# AUDIO_CODEC.net
KiCad netlist of a schematic drawn in Altium Designer
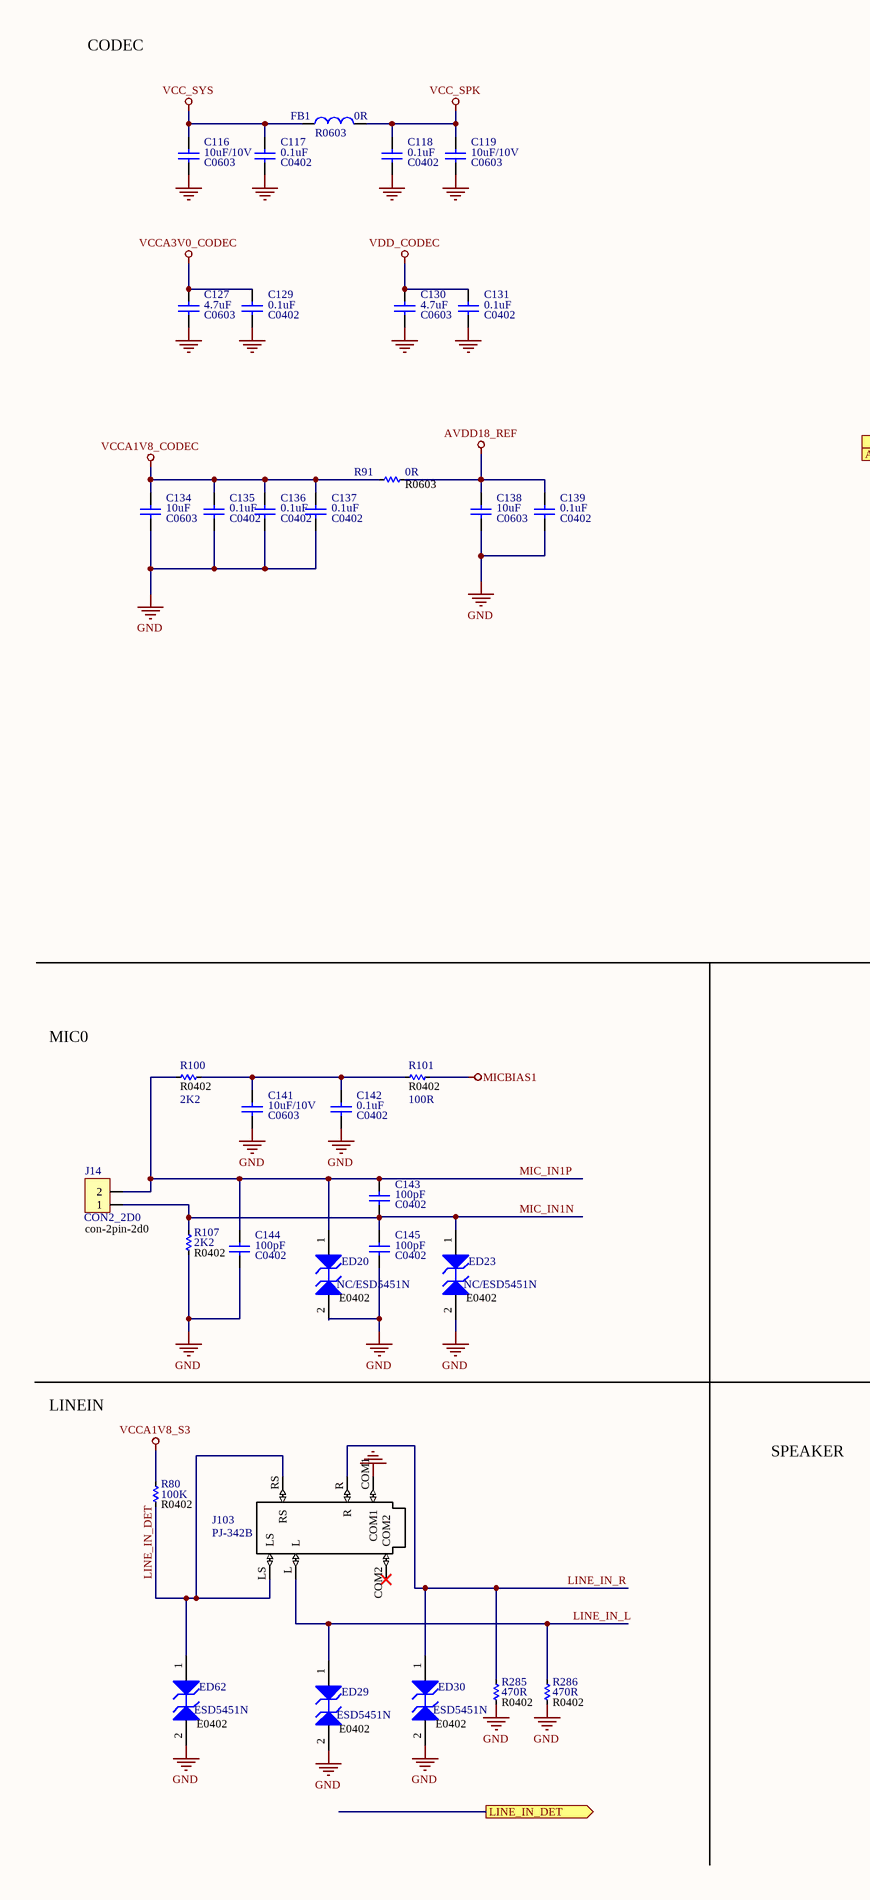
[diagram p0: AUDIO_CODEC.SchDoc, left]
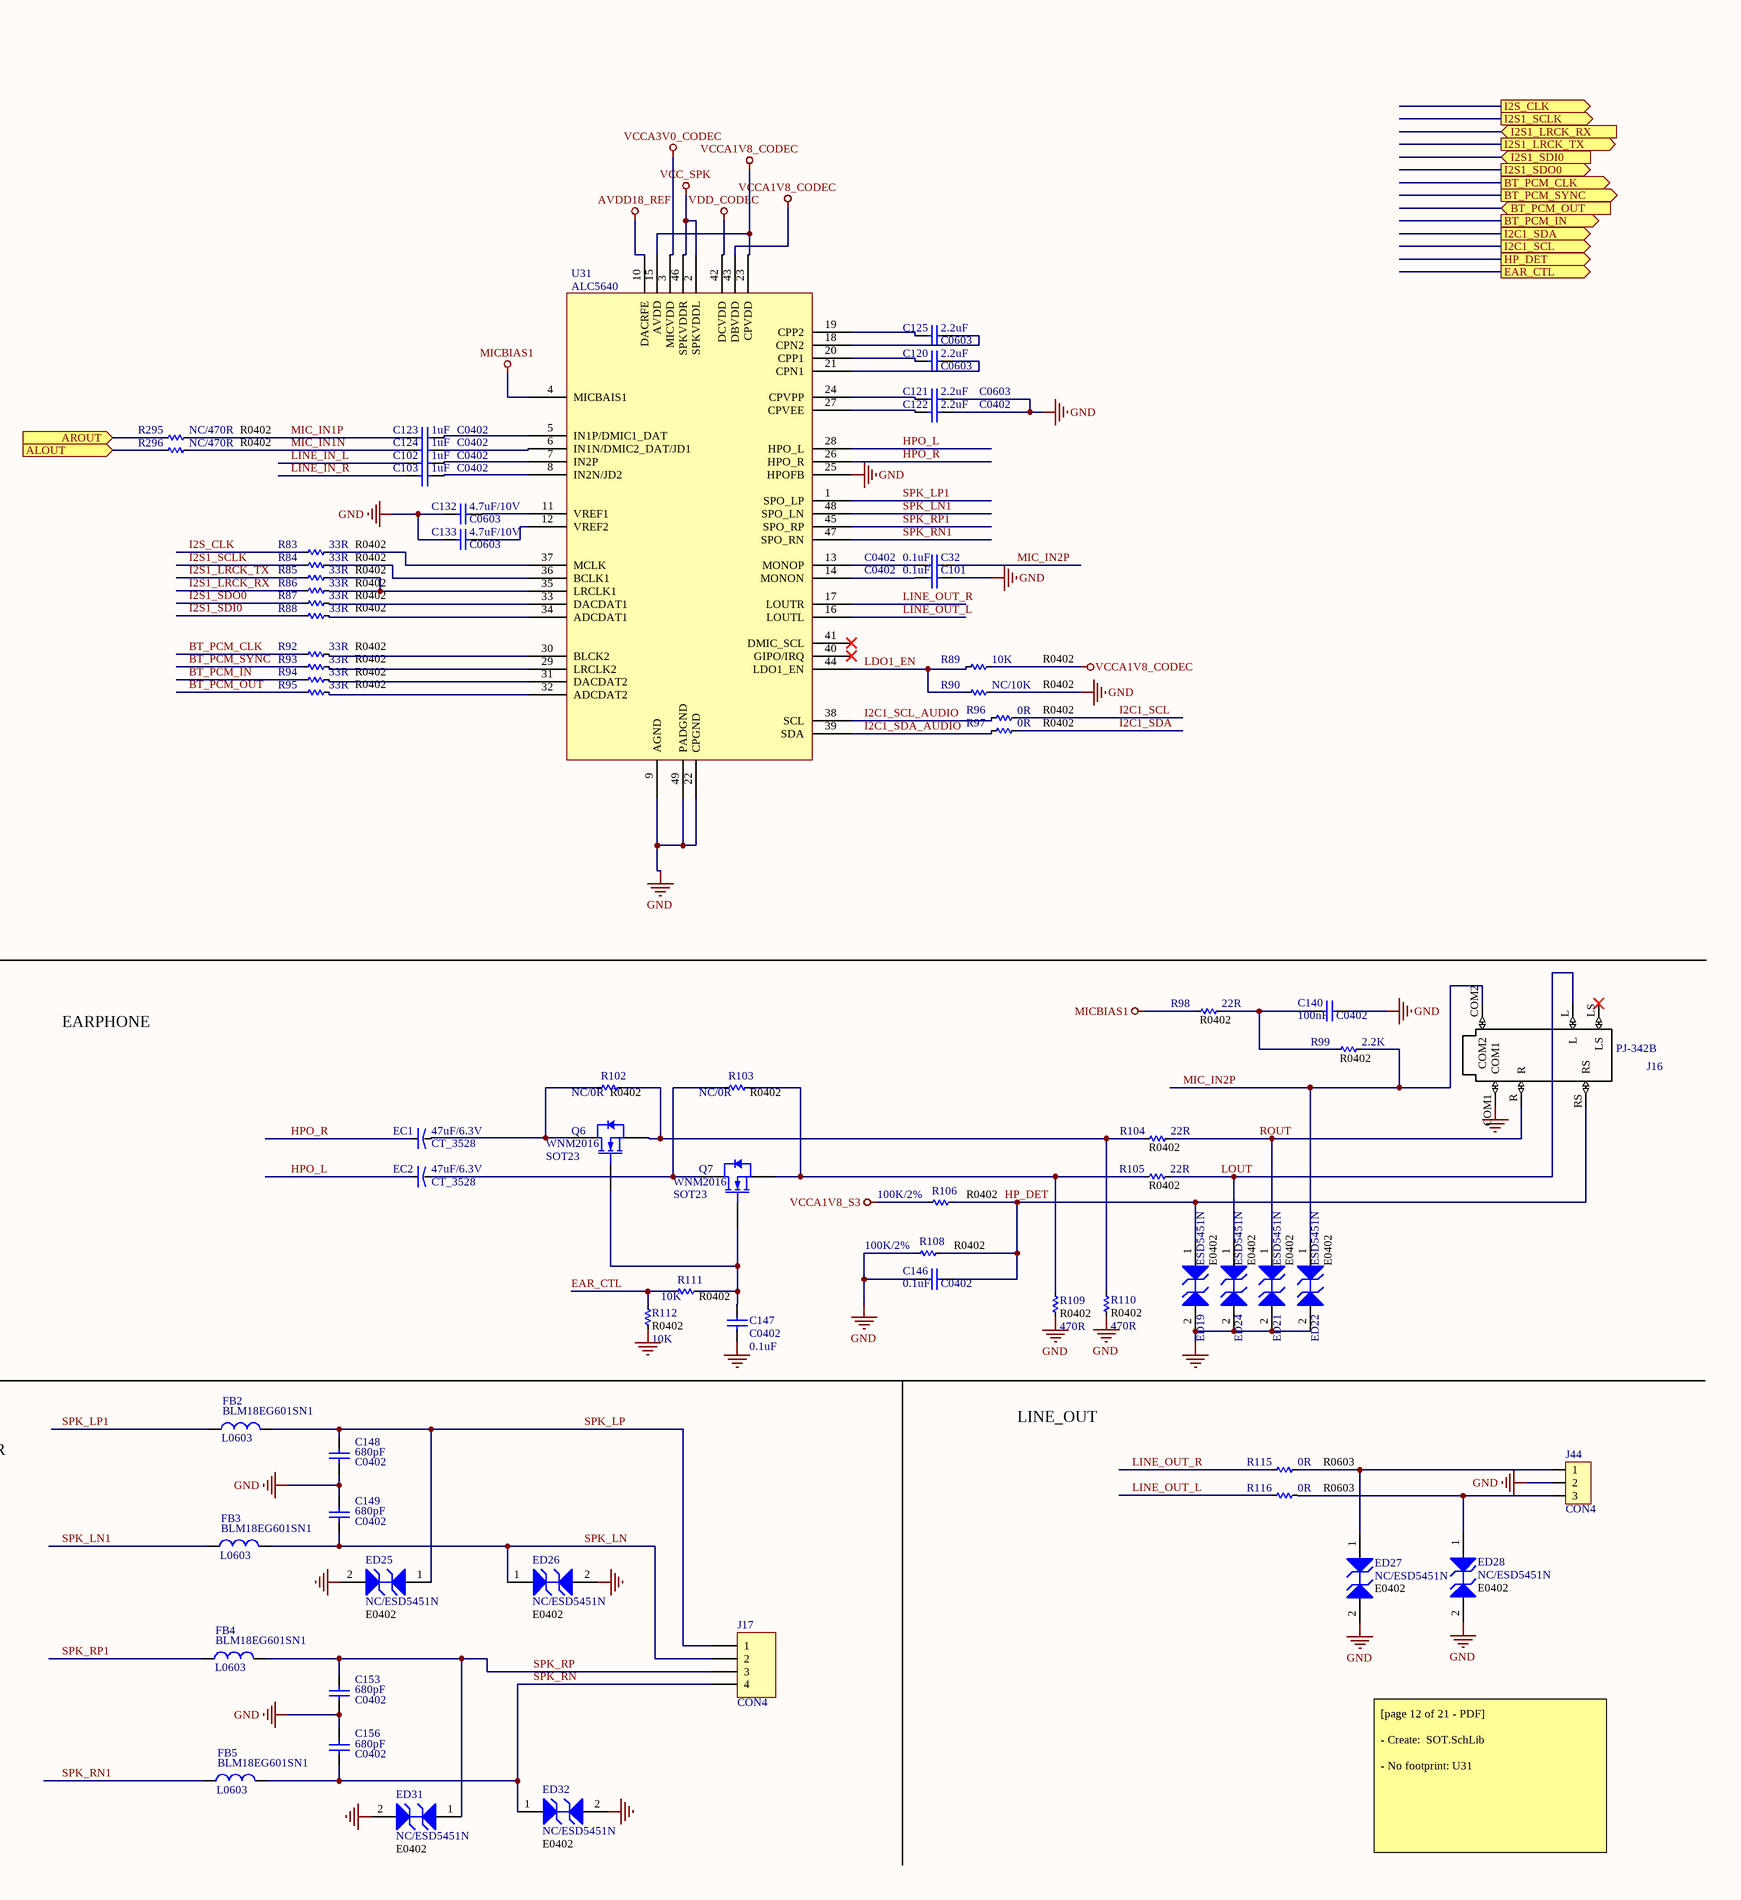
[diagram p1: AUDIO_CODEC.SchDoc, right]

(export (version "E")
  (design (tool "Eeschema 10.0.6"))
  (components
    (comp (ref "C32")
      (value "C0402")
      (footprint "C 0402")
      (description "Capacitor")
      (fields (field (name "ALTIUM_VALUE") "0.1uF") (field (name "PUBLISHER") "Altium Limited"))
      (libsource (lib "Miscellaneous Devices") (part "Cap"))
    )
    (comp (ref "C101")
      (value "C0402")
      (footprint "C 0402")
      (description "Capacitor")
      (fields (field (name "ALTIUM_VALUE") "0.1uF") (field (name "PUBLISHER") "Altium Limited"))
      (libsource (lib "Miscellaneous Devices") (part "Cap"))
    )
    (comp (ref "C102")
      (value "C0402")
      (footprint "C 0402")
      (description "Capacitor")
      (fields (field (name "ALTIUM_VALUE") "1uF") (field (name "PUBLISHER") "Altium Limited"))
      (libsource (lib "Miscellaneous Devices") (part "Cap"))
    )
    (comp (ref "C103")
      (value "C0402")
      (footprint "C 0402")
      (description "Capacitor")
      (fields (field (name "ALTIUM_VALUE") "1uF") (field (name "PUBLISHER") "Altium Limited"))
      (libsource (lib "Miscellaneous Devices") (part "Cap"))
    )
    (comp (ref "C116")
      (value "C0603")
      (footprint "C 0603")
      (description "Capacitor")
      (fields (field (name "ALTIUM_VALUE") "10uF/10V") (field (name "PUBLISHER") "Altium Limited"))
      (libsource (lib "Miscellaneous Devices") (part "Cap"))
    )
    (comp (ref "C117")
      (value "C0402")
      (footprint "C 0402")
      (description "Capacitor")
      (fields (field (name "ALTIUM_VALUE") "0.1uF") (field (name "PUBLISHER") "Altium Limited"))
      (libsource (lib "Miscellaneous Devices") (part "Cap"))
    )
    (comp (ref "C118")
      (value "C0402")
      (footprint "C 0402")
      (description "Capacitor")
      (fields (field (name "ALTIUM_VALUE") "0.1uF") (field (name "PUBLISHER") "Altium Limited"))
      (libsource (lib "Miscellaneous Devices") (part "Cap"))
    )
    (comp (ref "C119")
      (value "C0603")
      (footprint "C 0603")
      (description "Capacitor")
      (fields (field (name "ALTIUM_VALUE") "10uF/10V") (field (name "PUBLISHER") "Altium Limited"))
      (libsource (lib "Miscellaneous Devices") (part "Cap"))
    )
    (comp (ref "C120")
      (value "C0603")
      (footprint "C 0603")
      (description "Capacitor")
      (fields (field (name "ALTIUM_VALUE") "2.2uF") (field (name "PUBLISHER") "Altium Limited"))
      (libsource (lib "Miscellaneous Devices") (part "Cap"))
    )
    (comp (ref "C121")
      (value "C0603")
      (footprint "C 0603")
      (description "Capacitor")
      (fields (field (name "ALTIUM_VALUE") "2.2uF") (field (name "PUBLISHER") "Altium Limited"))
      (libsource (lib "Miscellaneous Devices") (part "Cap"))
    )
    (comp (ref "C122")
      (value "C0402")
      (footprint "C 0402")
      (description "Capacitor")
      (fields (field (name "ALTIUM_VALUE") "2.2uF") (field (name "PUBLISHER") "Altium Limited"))
      (libsource (lib "Miscellaneous Devices") (part "Cap"))
    )
    (comp (ref "C123")
      (value "C0402")
      (footprint "C 0402")
      (description "Capacitor")
      (fields (field (name "ALTIUM_VALUE") "1uF") (field (name "PUBLISHER") "Altium Limited"))
      (libsource (lib "Miscellaneous Devices") (part "Cap"))
    )
    (comp (ref "C124")
      (value "C0402")
      (footprint "C 0402")
      (description "Capacitor")
      (fields (field (name "ALTIUM_VALUE") "1uF") (field (name "PUBLISHER") "Altium Limited"))
      (libsource (lib "Miscellaneous Devices") (part "Cap"))
    )
    (comp (ref "C125")
      (value "C0603")
      (footprint "C 0603")
      (description "Capacitor")
      (fields (field (name "ALTIUM_VALUE") "2.2uF") (field (name "PUBLISHER") "Altium Limited"))
      (libsource (lib "Miscellaneous Devices") (part "Cap"))
    )
    (comp (ref "C127")
      (value "C0603")
      (footprint "C 0603")
      (description "Capacitor")
      (fields (field (name "ALTIUM_VALUE") "4.7uF") (field (name "PUBLISHER") "Altium Limited"))
      (libsource (lib "Miscellaneous Devices") (part "Cap"))
    )
    (comp (ref "C129")
      (value "C0402")
      (footprint "C 0402")
      (description "Capacitor")
      (fields (field (name "ALTIUM_VALUE") "0.1uF") (field (name "PUBLISHER") "Altium Limited"))
      (libsource (lib "Miscellaneous Devices") (part "Cap"))
    )
    (comp (ref "C130")
      (value "C0603")
      (footprint "C 0603")
      (description "Capacitor")
      (fields (field (name "ALTIUM_VALUE") "4.7uF") (field (name "PUBLISHER") "Altium Limited"))
      (libsource (lib "Miscellaneous Devices") (part "Cap"))
    )
    (comp (ref "C131")
      (value "C0402")
      (footprint "C 0402")
      (description "Capacitor")
      (fields (field (name "ALTIUM_VALUE") "0.1uF") (field (name "PUBLISHER") "Altium Limited"))
      (libsource (lib "Miscellaneous Devices") (part "Cap"))
    )
    (comp (ref "C132")
      (value "C0603")
      (footprint "C 0603")
      (description "Capacitor")
      (fields (field (name "ALTIUM_VALUE") "4.7uF/10V") (field (name "PUBLISHER") "Altium Limited"))
      (libsource (lib "Miscellaneous Devices") (part "Cap"))
    )
    (comp (ref "C133")
      (value "C0603")
      (footprint "C 0603")
      (description "Capacitor")
      (fields (field (name "ALTIUM_VALUE") "4.7uF/10V") (field (name "PUBLISHER") "Altium Limited"))
      (libsource (lib "Miscellaneous Devices") (part "Cap"))
    )
    (comp (ref "C134")
      (value "C0603")
      (footprint "C 0603")
      (description "Capacitor")
      (fields (field (name "ALTIUM_VALUE") "10uF") (field (name "PUBLISHER") "Altium Limited"))
      (libsource (lib "Miscellaneous Devices") (part "Cap"))
    )
    (comp (ref "C135")
      (value "C0402")
      (footprint "C 0402")
      (description "Capacitor")
      (fields (field (name "ALTIUM_VALUE") "0.1uF") (field (name "PUBLISHER") "Altium Limited"))
      (libsource (lib "Miscellaneous Devices") (part "Cap"))
    )
    (comp (ref "C136")
      (value "C0402")
      (footprint "C 0402")
      (description "Capacitor")
      (fields (field (name "ALTIUM_VALUE") "0.1uF") (field (name "PUBLISHER") "Altium Limited"))
      (libsource (lib "Miscellaneous Devices") (part "Cap"))
    )
    (comp (ref "C137")
      (value "C0402")
      (footprint "C 0402")
      (description "Capacitor")
      (fields (field (name "ALTIUM_VALUE") "0.1uF") (field (name "PUBLISHER") "Altium Limited"))
      (libsource (lib "Miscellaneous Devices") (part "Cap"))
    )
    (comp (ref "C138")
      (value "C0603")
      (footprint "C 0603")
      (description "Capacitor")
      (fields (field (name "ALTIUM_VALUE") "10uF") (field (name "PUBLISHER") "Altium Limited"))
      (libsource (lib "Miscellaneous Devices") (part "Cap"))
    )
    (comp (ref "C139")
      (value "C0402")
      (footprint "C 0402")
      (description "Capacitor")
      (fields (field (name "ALTIUM_VALUE") "0.1uF") (field (name "PUBLISHER") "Altium Limited"))
      (libsource (lib "Miscellaneous Devices") (part "Cap"))
    )
    (comp (ref "C140")
      (value "C0402")
      (footprint "C 0402")
      (description "Capacitor")
      (fields (field (name "ALTIUM_VALUE") "100nF") (field (name "PUBLISHER") "Altium Limited"))
      (libsource (lib "Miscellaneous Devices") (part "Cap"))
    )
    (comp (ref "C141")
      (value "C0603")
      (footprint "C 0603")
      (description "Capacitor")
      (fields (field (name "ALTIUM_VALUE") "10uF/10V") (field (name "PUBLISHER") "Altium Limited"))
      (libsource (lib "Miscellaneous Devices") (part "Cap"))
    )
    (comp (ref "C142")
      (value "C0402")
      (footprint "C 0402")
      (description "Capacitor")
      (fields (field (name "ALTIUM_VALUE") "0.1uF") (field (name "PUBLISHER") "Altium Limited"))
      (libsource (lib "Miscellaneous Devices") (part "Cap"))
    )
    (comp (ref "C143")
      (value "C0402")
      (footprint "C 0402")
      (description "Capacitor")
      (fields (field (name "ALTIUM_VALUE") "100pF") (field (name "PUBLISHER") "Altium Limited"))
      (libsource (lib "Miscellaneous Devices") (part "Cap"))
    )
    (comp (ref "C144")
      (value "C0402")
      (footprint "C 0402")
      (description "Capacitor")
      (fields (field (name "ALTIUM_VALUE") "100pF") (field (name "PUBLISHER") "Altium Limited"))
      (libsource (lib "Miscellaneous Devices") (part "Cap"))
    )
    (comp (ref "C145")
      (value "C0402")
      (footprint "C 0402")
      (description "Capacitor")
      (fields (field (name "ALTIUM_VALUE") "100pF") (field (name "PUBLISHER") "Altium Limited"))
      (libsource (lib "Miscellaneous Devices") (part "Cap"))
    )
    (comp (ref "C146")
      (value "C0402")
      (footprint "C 0402")
      (description "Capacitor")
      (fields (field (name "ALTIUM_VALUE") "0.1uF") (field (name "PUBLISHER") "Altium Limited"))
      (libsource (lib "Miscellaneous Devices") (part "Cap"))
    )
    (comp (ref "C147")
      (value "C0402")
      (footprint "C 0402")
      (description "Capacitor")
      (fields (field (name "ALTIUM_VALUE") "0.1uF") (field (name "PUBLISHER") "Altium Limited"))
      (libsource (lib "Miscellaneous Devices") (part "Cap"))
    )
    (comp (ref "C148")
      (value "C0402")
      (footprint "C 0402")
      (description "Capacitor")
      (fields (field (name "ALTIUM_VALUE") "680pF") (field (name "PUBLISHER") "Altium Limited"))
      (libsource (lib "Miscellaneous Devices") (part "Cap"))
    )
    (comp (ref "C149")
      (value "C0402")
      (footprint "C 0402")
      (description "Capacitor")
      (fields (field (name "ALTIUM_VALUE") "680pF") (field (name "PUBLISHER") "Altium Limited"))
      (libsource (lib "Miscellaneous Devices") (part "Cap"))
    )
    (comp (ref "C153")
      (value "C0402")
      (footprint "C 0402")
      (description "Capacitor")
      (fields (field (name "ALTIUM_VALUE") "680pF") (field (name "PUBLISHER") "Altium Limited"))
      (libsource (lib "Miscellaneous Devices") (part "Cap"))
    )
    (comp (ref "C156")
      (value "C0402")
      (footprint "C 0402")
      (description "Capacitor")
      (fields (field (name "ALTIUM_VALUE") "680pF") (field (name "PUBLISHER") "Altium Limited"))
      (libsource (lib "Miscellaneous Devices") (part "Cap"))
    )
    (comp (ref "EC1")
      (value "47uF/6.3V")
      (footprint "CAP-ALU-SMD-4.5x5x1.4")
      (description "Polarized Capacitor (Axial)")
      (fields
        (field (name "PACKAGE") "CT_3528")
        (field (name "Comment") "CN-ALU-SMD")
        (field (name "PUBLISHER") "Altium Limited")
      )
      (libsource (lib "LIBRARY") (part "CN-ALU-SMD"))
    )
    (comp (ref "EC2")
      (value "47uF/6.3V")
      (footprint "CAP-ALU-SMD-4.5x5x1.4")
      (description "Polarized Capacitor (Axial)")
      (fields
        (field (name "PACKAGE") "CT_3528")
        (field (name "Comment") "CN-ALU-SMD")
        (field (name "PUBLISHER") "Altium Limited")
      )
      (libsource (lib "LIBRARY") (part "CN-ALU-SMD"))
    )
    (comp (ref "ED19")
      (value "ESD5451N")
      (footprint "DFN1006-2L")
      (description "600 W Peak Power Zener Transient Voltage Suppressor, Bidirectional, 2-Pin SMB, Tape and Reel")
      (fields
        (field (name "MANUFACTURER") "On Semiconductor")
        (field (name "PARTNUMBER") "1SMB54CAT3")
        (field (name "ALTIUM_UNNAMED_1") "E0402")
      )
      (libsource (lib "ON Semi Transient Voltage Suppressors (TVS)") (part "1SMB54CAT3"))
    )
    (comp (ref "ED20")
      (value "NC/ESD5451N")
      (footprint "DFN1006-2L")
      (description "600 W Peak Power Zener Transient Voltage Suppressor, Bidirectional, 2-Pin SMB, Tape and Reel")
      (fields
        (field (name "MANUFACTURER") "On Semiconductor")
        (field (name "PARTNUMBER") "1SMB54CAT3")
        (field (name "ALTIUM_UNNAMED_1") "E0402")
      )
      (libsource (lib "ON Semi Transient Voltage Suppressors (TVS)") (part "1SMB54CAT3"))
    )
    (comp (ref "ED21")
      (value "ESD5451N")
      (footprint "DFN1006-2L")
      (description "600 W Peak Power Zener Transient Voltage Suppressor, Bidirectional, 2-Pin SMB, Tape and Reel")
      (fields
        (field (name "MANUFACTURER") "On Semiconductor")
        (field (name "PARTNUMBER") "1SMB54CAT3")
        (field (name "ALTIUM_UNNAMED_1") "E0402")
      )
      (libsource (lib "ON Semi Transient Voltage Suppressors (TVS)") (part "1SMB54CAT3"))
    )
    (comp (ref "ED22")
      (value "ESD5451N")
      (footprint "DFN1006-2L")
      (description "600 W Peak Power Zener Transient Voltage Suppressor, Bidirectional, 2-Pin SMB, Tape and Reel")
      (fields
        (field (name "MANUFACTURER") "On Semiconductor")
        (field (name "PARTNUMBER") "1SMB54CAT3")
        (field (name "ALTIUM_UNNAMED_1") "E0402")
      )
      (libsource (lib "ON Semi Transient Voltage Suppressors (TVS)") (part "1SMB54CAT3"))
    )
    (comp (ref "ED23")
      (value "NC/ESD5451N")
      (footprint "DFN1006-2L")
      (description "600 W Peak Power Zener Transient Voltage Suppressor, Bidirectional, 2-Pin SMB, Tape and Reel")
      (fields
        (field (name "MANUFACTURER") "On Semiconductor")
        (field (name "PARTNUMBER") "1SMB54CAT3")
        (field (name "ALTIUM_UNNAMED_1") "E0402")
      )
      (libsource (lib "ON Semi Transient Voltage Suppressors (TVS)") (part "1SMB54CAT3"))
    )
    (comp (ref "ED24")
      (value "ESD5451N")
      (footprint "DFN1006-2L")
      (description "600 W Peak Power Zener Transient Voltage Suppressor, Bidirectional, 2-Pin SMB, Tape and Reel")
      (fields
        (field (name "MANUFACTURER") "On Semiconductor")
        (field (name "PARTNUMBER") "1SMB54CAT3")
        (field (name "ALTIUM_UNNAMED_1") "E0402")
      )
      (libsource (lib "ON Semi Transient Voltage Suppressors (TVS)") (part "1SMB54CAT3"))
    )
    (comp (ref "ED25")
      (value "NC/ESD5451N")
      (footprint "DFN1006-2L")
      (description "600 W Peak Power Zener Transient Voltage Suppressor, Bidirectional, 2-Pin SMB, Tape and Reel")
      (fields
        (field (name "MANUFACTURER") "On Semiconductor")
        (field (name "PARTNUMBER") "1SMB54CAT3")
        (field (name "ALTIUM_UNNAMED_1") "E0402")
      )
      (libsource (lib "ON Semi Transient Voltage Suppressors (TVS)") (part "1SMB54CAT3"))
    )
    (comp (ref "ED26")
      (value "NC/ESD5451N")
      (footprint "DFN1006-2L")
      (description "600 W Peak Power Zener Transient Voltage Suppressor, Bidirectional, 2-Pin SMB, Tape and Reel")
      (fields
        (field (name "MANUFACTURER") "On Semiconductor")
        (field (name "PARTNUMBER") "1SMB54CAT3")
        (field (name "ALTIUM_UNNAMED_1") "E0402")
      )
      (libsource (lib "ON Semi Transient Voltage Suppressors (TVS)") (part "1SMB54CAT3"))
    )
    (comp (ref "ED27")
      (value "NC/ESD5451N")
      (footprint "DFN1006-2L")
      (description "600 W Peak Power Zener Transient Voltage Suppressor, Bidirectional, 2-Pin SMB, Tape and Reel")
      (fields
        (field (name "MANUFACTURER") "On Semiconductor")
        (field (name "PARTNUMBER") "1SMB54CAT3")
        (field (name "ALTIUM_UNNAMED_1") "E0402")
      )
      (libsource (lib "ON Semi Transient Voltage Suppressors (TVS)") (part "1SMB54CAT3"))
    )
    (comp (ref "ED28")
      (value "NC/ESD5451N")
      (footprint "DFN1006-2L")
      (description "600 W Peak Power Zener Transient Voltage Suppressor, Bidirectional, 2-Pin SMB, Tape and Reel")
      (fields
        (field (name "MANUFACTURER") "On Semiconductor")
        (field (name "PARTNUMBER") "1SMB54CAT3")
        (field (name "ALTIUM_UNNAMED_1") "E0402")
      )
      (libsource (lib "ON Semi Transient Voltage Suppressors (TVS)") (part "1SMB54CAT3"))
    )
    (comp (ref "ED29")
      (value "ESD5451N")
      (footprint "DFN1006-2L")
      (description "600 W Peak Power Zener Transient Voltage Suppressor, Bidirectional, 2-Pin SMB, Tape and Reel")
      (fields
        (field (name "MANUFACTURER") "On Semiconductor")
        (field (name "PARTNUMBER") "1SMB54CAT3")
        (field (name "ALTIUM_UNNAMED_1") "E0402")
      )
      (libsource (lib "ON Semi Transient Voltage Suppressors (TVS)") (part "1SMB54CAT3"))
    )
    (comp (ref "ED30")
      (value "ESD5451N")
      (footprint "DFN1006-2L")
      (description "600 W Peak Power Zener Transient Voltage Suppressor, Bidirectional, 2-Pin SMB, Tape and Reel")
      (fields
        (field (name "MANUFACTURER") "On Semiconductor")
        (field (name "PARTNUMBER") "1SMB54CAT3")
        (field (name "ALTIUM_UNNAMED_1") "E0402")
      )
      (libsource (lib "ON Semi Transient Voltage Suppressors (TVS)") (part "1SMB54CAT3"))
    )
    (comp (ref "ED31")
      (value "NC/ESD5451N")
      (footprint "DFN1006-2L")
      (description "600 W Peak Power Zener Transient Voltage Suppressor, Bidirectional, 2-Pin SMB, Tape and Reel")
      (fields
        (field (name "MANUFACTURER") "On Semiconductor")
        (field (name "PARTNUMBER") "1SMB54CAT3")
        (field (name "ALTIUM_UNNAMED_1") "E0402")
      )
      (libsource (lib "ON Semi Transient Voltage Suppressors (TVS)") (part "1SMB54CAT3"))
    )
    (comp (ref "ED32")
      (value "NC/ESD5451N")
      (footprint "DFN1006-2L")
      (description "600 W Peak Power Zener Transient Voltage Suppressor, Bidirectional, 2-Pin SMB, Tape and Reel")
      (fields
        (field (name "MANUFACTURER") "On Semiconductor")
        (field (name "PARTNUMBER") "1SMB54CAT3")
        (field (name "ALTIUM_UNNAMED_1") "E0402")
      )
      (libsource (lib "ON Semi Transient Voltage Suppressors (TVS)") (part "1SMB54CAT3"))
    )
    (comp (ref "ED62")
      (value "ESD5451N")
      (footprint "DFN1006-2L")
      (description "600 W Peak Power Zener Transient Voltage Suppressor, Bidirectional, 2-Pin SMB, Tape and Reel")
      (fields
        (field (name "MANUFACTURER") "On Semiconductor")
        (field (name "PARTNUMBER") "1SMB54CAT3")
        (field (name "ALTIUM_UNNAMED_1") "E0402")
      )
      (libsource (lib "ON Semi Transient Voltage Suppressors (TVS)") (part "1SMB54CAT3"))
    )
    (comp (ref "FB1")
      (value "R0603")
      (footprint "L/0.4")
      (description "Inductor")
      (fields (field (name "ALTIUM_UNNAMED_1") "0R"))
      (libsource (lib "syhaunguyen") (part "L1"))
    )
    (comp (ref "FB2")
      (value "L0603")
      (footprint "L/0.4")
      (description "Inductor")
      (fields (field (name "ALTIUM_UNNAMED_1") "BLM18EG601SN1"))
      (libsource (lib "syhaunguyen") (part "L1"))
    )
    (comp (ref "FB3")
      (value "L0603")
      (footprint "L/0.4")
      (description "Inductor")
      (fields (field (name "ALTIUM_UNNAMED_1") "BLM18EG601SN1"))
      (libsource (lib "syhaunguyen") (part "L1"))
    )
    (comp (ref "FB4")
      (value "L0603")
      (footprint "L/0.4")
      (description "Inductor")
      (fields (field (name "ALTIUM_UNNAMED_1") "BLM18EG601SN1"))
      (libsource (lib "syhaunguyen") (part "L1"))
    )
    (comp (ref "FB5")
      (value "L0603")
      (footprint "L/0.4")
      (description "Inductor")
      (fields (field (name "ALTIUM_UNNAMED_1") "BLM18EG601SN1"))
      (libsource (lib "syhaunguyen") (part "L1"))
    )
    (comp (ref "J14")
      (value "CON2_2D0")
      (footprint "Header2")
      (description "Header IDC, 2 x 1 Pin Vertical 2.54mm Pitch (Non-Boxed, Male)")
      (fields
        (field (name "MANUFACTURER") "Würth Elektronik eiSos GmbH")
        (field (name "PARTNO") "613002143121")
        (field (name "ALTIUM_UNNAMED_1") "con-2pin-2d0")
        (field (name "CREATED BY") "Karrer Zheng")
      )
      (libsource (lib "LIBRARY") (part "Header2"))
    )
    (comp (ref "J16")
      (value "PJ-342B")
      (footprint "*SUNTECH_ST-PJ-312_ST-PJ-312(Primary)")
      (description "SMD Audio Jack; 3.5mm")
      (fields (field (name "MF") "Suntech") (field (name "MP") "ST-PJ-312"))
      (libsource (lib "ST-PJ-312") (part "ST-PJ-312"))
    )
    (comp (ref "J17")
      (value "CON4")
      (footprint "CON4")
      (description "Header, 4-Pin")
      (fields (field (name "PUBLISHER") "Altium Limited"))
      (libsource (lib "Miscellaneous Connectors") (part "Header 4"))
    )
    (comp (ref "J44")
      (value "CON4")
      (footprint "Header3")
      (description "Header IDC, 3 x 1 Pin Vertical 2.54mm Pitch (Non-Boxed, Male)")
      (fields
        (field (name "MANUFACTURER") "Würth Elektronik eiSos GmbH")
        (field (name "PARTNO") "613002143121")
        (field (name "CREATED BY") "Karrer Zheng")
      )
      (libsource (lib "LIBRARY") (part "Header3"))
    )
    (comp (ref "J103")
      (value "PJ-342B")
      (footprint "*SUNTECH_ST-PJ-312_ST-PJ-312(Primary)")
      (description "SMD Audio Jack; 3.5mm")
      (fields (field (name "MF") "Suntech") (field (name "MP") "ST-PJ-312"))
      (libsource (lib "") (part "ST-PJ-312_1"))
    )
    (comp (ref "Q6")
      (value "WNM2016")
      (footprint "SOT23")
      (description "20V N-Channel Enhancement Mode MOSFET")
      (fields (field (name "PACKAGEREFERENCE") "SOT23") (field (name "PUBLISHER") "Altium Limited"))
      (libsource (lib "Zetex Discrete MOSFET") (part "ZXM61N02F"))
    )
    (comp (ref "Q7")
      (value "WNM2016")
      (footprint "SOT23")
      (description "20V N-Channel Enhancement Mode MOSFET")
      (fields (field (name "PACKAGEREFERENCE") "SOT23") (field (name "PUBLISHER") "Altium Limited"))
      (libsource (lib "Zetex Discrete MOSFET") (part "ZXM61N02F"))
    )
    (comp (ref "R80")
      (value "R0402")
      (footprint "R 0402")
      (description "Resistor")
      (fields
        (field (name "MANUFACTURER") "Generic Components")
        (field (name "ALTIUM_VALUE") "100K")
        (field (name "PUBLISHER") "Altium Hobart Technology Centre")
      )
      (libsource (lib "LIBRARY") (part "Res-SMD"))
    )
    (comp (ref "R83")
      (value "R0402")
      (footprint "R 0402")
      (description "Resistor")
      (fields
        (field (name "MANUFACTURER") "Generic Components")
        (field (name "ALTIUM_VALUE") "33R")
        (field (name "PUBLISHER") "Altium Hobart Technology Centre")
      )
      (libsource (lib "LIBRARY") (part "Res-SMD"))
    )
    (comp (ref "R84")
      (value "R0402")
      (footprint "R 0402")
      (description "Resistor")
      (fields
        (field (name "MANUFACTURER") "Generic Components")
        (field (name "ALTIUM_VALUE") "33R")
        (field (name "PUBLISHER") "Altium Hobart Technology Centre")
      )
      (libsource (lib "LIBRARY") (part "Res-SMD"))
    )
    (comp (ref "R85")
      (value "R0402")
      (footprint "R 0402")
      (description "Resistor")
      (fields
        (field (name "MANUFACTURER") "Generic Components")
        (field (name "ALTIUM_VALUE") "33R")
        (field (name "PUBLISHER") "Altium Hobart Technology Centre")
      )
      (libsource (lib "LIBRARY") (part "Res-SMD"))
    )
    (comp (ref "R86")
      (value "R0402")
      (footprint "R 0402")
      (description "Resistor")
      (fields
        (field (name "MANUFACTURER") "Generic Components")
        (field (name "ALTIUM_VALUE") "33R")
        (field (name "PUBLISHER") "Altium Hobart Technology Centre")
      )
      (libsource (lib "LIBRARY") (part "Res-SMD"))
    )
    (comp (ref "R87")
      (value "R0402")
      (footprint "R 0402")
      (description "Resistor")
      (fields
        (field (name "MANUFACTURER") "Generic Components")
        (field (name "ALTIUM_VALUE") "33R")
        (field (name "PUBLISHER") "Altium Hobart Technology Centre")
      )
      (libsource (lib "LIBRARY") (part "Res-SMD"))
    )
    (comp (ref "R88")
      (value "R0402")
      (footprint "R 0402")
      (description "Resistor")
      (fields
        (field (name "MANUFACTURER") "Generic Components")
        (field (name "ALTIUM_VALUE") "33R")
        (field (name "PUBLISHER") "Altium Hobart Technology Centre")
      )
      (libsource (lib "LIBRARY") (part "Res-SMD"))
    )
    (comp (ref "R89")
      (value "R0402")
      (footprint "R 0402")
      (description "Resistor")
      (fields
        (field (name "MANUFACTURER") "Generic Components")
        (field (name "ALTIUM_VALUE") "10K")
        (field (name "PUBLISHER") "Altium Hobart Technology Centre")
      )
      (libsource (lib "LIBRARY") (part "Res-SMD"))
    )
    (comp (ref "R90")
      (value "R0402")
      (footprint "R 0402")
      (description "Resistor")
      (fields
        (field (name "MANUFACTURER") "Generic Components")
        (field (name "ALTIUM_VALUE") "NC/10K")
        (field (name "PUBLISHER") "Altium Hobart Technology Centre")
      )
      (libsource (lib "LIBRARY") (part "Res-SMD"))
    )
    (comp (ref "R91")
      (value "R0603")
      (footprint "R 0603")
      (description "Resistor")
      (fields
        (field (name "MANUFACTURER") "Generic Components")
        (field (name "ALTIUM_VALUE") "0R")
        (field (name "PUBLISHER") "Altium Hobart Technology Centre")
      )
      (libsource (lib "LIBRARY") (part "Res-SMD"))
    )
    (comp (ref "R92")
      (value "R0402")
      (footprint "R 0402")
      (description "Resistor")
      (fields
        (field (name "MANUFACTURER") "Generic Components")
        (field (name "ALTIUM_VALUE") "33R")
        (field (name "PUBLISHER") "Altium Hobart Technology Centre")
      )
      (libsource (lib "LIBRARY") (part "Res-SMD"))
    )
    (comp (ref "R93")
      (value "R0402")
      (footprint "R 0402")
      (description "Resistor")
      (fields
        (field (name "MANUFACTURER") "Generic Components")
        (field (name "ALTIUM_VALUE") "33R")
        (field (name "PUBLISHER") "Altium Hobart Technology Centre")
      )
      (libsource (lib "LIBRARY") (part "Res-SMD"))
    )
    (comp (ref "R94")
      (value "R0402")
      (footprint "R 0402")
      (description "Resistor")
      (fields
        (field (name "MANUFACTURER") "Generic Components")
        (field (name "ALTIUM_VALUE") "33R")
        (field (name "PUBLISHER") "Altium Hobart Technology Centre")
      )
      (libsource (lib "LIBRARY") (part "Res-SMD"))
    )
    (comp (ref "R95")
      (value "R0402")
      (footprint "R 0402")
      (description "Resistor")
      (fields
        (field (name "MANUFACTURER") "Generic Components")
        (field (name "ALTIUM_VALUE") "33R")
        (field (name "PUBLISHER") "Altium Hobart Technology Centre")
      )
      (libsource (lib "LIBRARY") (part "Res-SMD"))
    )
    (comp (ref "R96")
      (value "R0402")
      (footprint "R 0402")
      (description "Resistor")
      (fields
        (field (name "MANUFACTURER") "Generic Components")
        (field (name "ALTIUM_VALUE") "0R")
        (field (name "PUBLISHER") "Altium Hobart Technology Centre")
      )
      (libsource (lib "LIBRARY") (part "Res-SMD"))
    )
    (comp (ref "R97")
      (value "R0402")
      (footprint "R 0402")
      (description "Resistor")
      (fields
        (field (name "MANUFACTURER") "Generic Components")
        (field (name "ALTIUM_VALUE") "0R")
        (field (name "PUBLISHER") "Altium Hobart Technology Centre")
      )
      (libsource (lib "LIBRARY") (part "Res-SMD"))
    )
    (comp (ref "R98")
      (value "R0402")
      (footprint "R 0402")
      (description "Resistor")
      (fields
        (field (name "MANUFACTURER") "Generic Components")
        (field (name "ALTIUM_VALUE") "22R")
        (field (name "PUBLISHER") "Altium Hobart Technology Centre")
      )
      (libsource (lib "LIBRARY") (part "Res-SMD"))
    )
    (comp (ref "R99")
      (value "R0402")
      (footprint "R 0402")
      (description "Resistor")
      (fields
        (field (name "MANUFACTURER") "Generic Components")
        (field (name "ALTIUM_VALUE") "2.2K")
        (field (name "PUBLISHER") "Altium Hobart Technology Centre")
      )
      (libsource (lib "LIBRARY") (part "Res-SMD"))
    )
    (comp (ref "R100")
      (value "R0402")
      (footprint "R 0402")
      (description "Resistor")
      (fields
        (field (name "MANUFACTURER") "Generic Components")
        (field (name "ALTIUM_VALUE") "2K2")
        (field (name "PUBLISHER") "Altium Hobart Technology Centre")
      )
      (libsource (lib "LIBRARY") (part "Res-SMD"))
    )
    (comp (ref "R101")
      (value "R0402")
      (footprint "R 0402")
      (description "Resistor")
      (fields
        (field (name "MANUFACTURER") "Generic Components")
        (field (name "ALTIUM_VALUE") "100R")
        (field (name "PUBLISHER") "Altium Hobart Technology Centre")
      )
      (libsource (lib "LIBRARY") (part "Res-SMD"))
    )
    (comp (ref "R102")
      (value "R0402")
      (footprint "R 0402")
      (description "Resistor")
      (fields
        (field (name "MANUFACTURER") "Generic Components")
        (field (name "ALTIUM_VALUE") "NC/0R")
        (field (name "PUBLISHER") "Altium Hobart Technology Centre")
      )
      (libsource (lib "LIBRARY") (part "Res-SMD"))
    )
    (comp (ref "R103")
      (value "R0402")
      (footprint "R 0402")
      (description "Resistor")
      (fields
        (field (name "MANUFACTURER") "Generic Components")
        (field (name "ALTIUM_VALUE") "NC/0R")
        (field (name "PUBLISHER") "Altium Hobart Technology Centre")
      )
      (libsource (lib "LIBRARY") (part "Res-SMD"))
    )
    (comp (ref "R104")
      (value "R0402")
      (footprint "R 0402")
      (description "Resistor")
      (fields
        (field (name "MANUFACTURER") "Generic Components")
        (field (name "ALTIUM_VALUE") "22R")
        (field (name "PUBLISHER") "Altium Hobart Technology Centre")
      )
      (libsource (lib "LIBRARY") (part "Res-SMD"))
    )
    (comp (ref "R105")
      (value "R0402")
      (footprint "R 0402")
      (description "Resistor")
      (fields
        (field (name "MANUFACTURER") "Generic Components")
        (field (name "ALTIUM_VALUE") "22R")
        (field (name "PUBLISHER") "Altium Hobart Technology Centre")
      )
      (libsource (lib "LIBRARY") (part "Res-SMD"))
    )
    (comp (ref "R106")
      (value "R0402")
      (footprint "R 0402")
      (description "Resistor")
      (fields
        (field (name "MANUFACTURER") "Generic Components")
        (field (name "ALTIUM_VALUE") "100K/2%")
        (field (name "PUBLISHER") "Altium Hobart Technology Centre")
      )
      (libsource (lib "LIBRARY") (part "Res-SMD"))
    )
    (comp (ref "R107")
      (value "R0402")
      (footprint "R 0402")
      (description "Resistor")
      (fields
        (field (name "MANUFACTURER") "Generic Components")
        (field (name "ALTIUM_VALUE") "2K2")
        (field (name "PUBLISHER") "Altium Hobart Technology Centre")
      )
      (libsource (lib "LIBRARY") (part "Res-SMD"))
    )
    (comp (ref "R108")
      (value "R0402")
      (footprint "R 0402")
      (description "Resistor")
      (fields
        (field (name "MANUFACTURER") "Generic Components")
        (field (name "ALTIUM_VALUE") "100K/2%")
        (field (name "PUBLISHER") "Altium Hobart Technology Centre")
      )
      (libsource (lib "LIBRARY") (part "Res-SMD"))
    )
    (comp (ref "R109")
      (value "R0402")
      (footprint "R 0402")
      (description "Resistor")
      (fields
        (field (name "MANUFACTURER") "Generic Components")
        (field (name "ALTIUM_VALUE") "470R")
        (field (name "PUBLISHER") "Altium Hobart Technology Centre")
      )
      (libsource (lib "LIBRARY") (part "Res-SMD"))
    )
    (comp (ref "R110")
      (value "R0402")
      (footprint "R 0402")
      (description "Resistor")
      (fields
        (field (name "MANUFACTURER") "Generic Components")
        (field (name "ALTIUM_VALUE") "470R")
        (field (name "PUBLISHER") "Altium Hobart Technology Centre")
      )
      (libsource (lib "LIBRARY") (part "Res-SMD"))
    )
    (comp (ref "R111")
      (value "R0402")
      (footprint "R 0402")
      (description "Resistor")
      (fields
        (field (name "MANUFACTURER") "Generic Components")
        (field (name "ALTIUM_VALUE") "10K")
        (field (name "PUBLISHER") "Altium Hobart Technology Centre")
      )
      (libsource (lib "LIBRARY") (part "Res-SMD"))
    )
    (comp (ref "R112")
      (value "R0402")
      (footprint "R 0402")
      (description "Resistor")
      (fields
        (field (name "MANUFACTURER") "Generic Components")
        (field (name "ALTIUM_VALUE") "10K")
        (field (name "PUBLISHER") "Altium Hobart Technology Centre")
      )
      (libsource (lib "LIBRARY") (part "Res-SMD"))
    )
    (comp (ref "R115")
      (value "R0603")
      (footprint "R 0603")
      (description "Resistor")
      (fields
        (field (name "MANUFACTURER") "Generic Components")
        (field (name "ALTIUM_VALUE") "0R")
        (field (name "PUBLISHER") "Altium Hobart Technology Centre")
      )
      (libsource (lib "LIBRARY") (part "Res-SMD"))
    )
    (comp (ref "R116")
      (value "R0603")
      (footprint "R 0603")
      (description "Resistor")
      (fields
        (field (name "MANUFACTURER") "Generic Components")
        (field (name "ALTIUM_VALUE") "0R")
        (field (name "PUBLISHER") "Altium Hobart Technology Centre")
      )
      (libsource (lib "LIBRARY") (part "Res-SMD"))
    )
    (comp (ref "R285")
      (value "R0402")
      (footprint "R 0402")
      (description "Resistor")
      (fields
        (field (name "MANUFACTURER") "Generic Components")
        (field (name "ALTIUM_VALUE") "470R")
        (field (name "PUBLISHER") "Altium Hobart Technology Centre")
      )
      (libsource (lib "LIBRARY") (part "Res-SMD"))
    )
    (comp (ref "R286")
      (value "R0402")
      (footprint "R 0402")
      (description "Resistor")
      (fields
        (field (name "MANUFACTURER") "Generic Components")
        (field (name "ALTIUM_VALUE") "470R")
        (field (name "PUBLISHER") "Altium Hobart Technology Centre")
      )
      (libsource (lib "LIBRARY") (part "Res-SMD"))
    )
    (comp (ref "R295")
      (value "R0402")
      (footprint "R 0402")
      (description "Resistor")
      (fields
        (field (name "MANUFACTURER") "Generic Components")
        (field (name "ALTIUM_VALUE") "NC/470R")
        (field (name "PUBLISHER") "Altium Hobart Technology Centre")
      )
      (libsource (lib "LIBRARY") (part "Res-SMD"))
    )
    (comp (ref "R296")
      (value "R0402")
      (footprint "R 0402")
      (description "Resistor")
      (fields
        (field (name "MANUFACTURER") "Generic Components")
        (field (name "ALTIUM_VALUE") "NC/470R")
        (field (name "PUBLISHER") "Altium Hobart Technology Centre")
      )
      (libsource (lib "LIBRARY") (part "Res-SMD"))
    )
    (comp (ref "U31") (value "ALC5640") (footprint "QFN48") (libsource (lib "SOT") (part "ALC5640")))
  )
  (nets
    (net (code "1") (name "/ALOUT") (class "Default")
      (node (ref "R296") (pin "1") (pinfunction "1_1") (pintype "passive"))
    )
    (net (code "2") (name "/AROUT") (class "Default")
      (node (ref "R295") (pin "1") (pinfunction "1_1") (pintype "passive"))
    )
    (net (code "3") (name "/BT_PCM_CLK") (class "Default")
      (node (ref "R92") (pin "1") (pinfunction "1_1") (pintype "passive"))
    )
    (net (code "4") (name "/BT_PCM_IN") (class "Default")
      (node (ref "R94") (pin "1") (pinfunction "1_1") (pintype "passive"))
    )
    (net (code "5") (name "/BT_PCM_OUT") (class "Default")
      (node (ref "R95") (pin "1") (pinfunction "1_1") (pintype "passive"))
    )
    (net (code "6") (name "/BT_PCM_SYNC") (class "Default")
      (node (ref "R93") (pin "1") (pinfunction "1_1") (pintype "passive"))
    )
    (net (code "7") (name "/EAR_CTL") (class "Default")
      (node (ref "R111") (pin "2") (pinfunction "2_2") (pintype "passive"))
      (node (ref "R112") (pin "1") (pinfunction "1_1") (pintype "passive"))
    )
    (net (code "8") (name "/HPO_L") (class "Default")
      (node (ref "EC2") (pin "1") (pinfunction "1_1") (pintype "passive"))
      (node (ref "U31") (pin "28") (pinfunction "HPO_L_28") (pintype "passive"))
    )
    (net (code "9") (name "/HPO_R") (class "Default")
      (node (ref "EC1") (pin "1") (pinfunction "1_1") (pintype "passive"))
      (node (ref "U31") (pin "26") (pinfunction "HPO_R_26") (pintype "passive"))
    )
    (net (code "10") (name "/HP_DET") (class "Default")
      (node (ref "C146") (pin "2") (pinfunction "2_2") (pintype "passive"))
      (node (ref "ED19") (pin "1") (pinfunction "A1_1") (pintype "passive"))
      (node (ref "J16") (pin "RS") (pinfunction "RS_RS") (pintype "bidirectional"))
      (node (ref "R106") (pin "1") (pinfunction "1_1") (pintype "passive"))
      (node (ref "R108") (pin "1") (pinfunction "1_1") (pintype "passive"))
    )
    (net (code "11") (name "/I2C1_SCL") (class "Default")
      (node (ref "R96") (pin "2") (pinfunction "2_2") (pintype "passive"))
    )
    (net (code "12") (name "/I2C1_SCL_AUDIO") (class "Default")
      (node (ref "R96") (pin "1") (pinfunction "1_1") (pintype "passive"))
      (node (ref "U31") (pin "38") (pinfunction "SCL_38") (pintype "passive"))
    )
    (net (code "13") (name "/I2C1_SDA") (class "Default")
      (node (ref "R97") (pin "2") (pinfunction "2_2") (pintype "passive"))
    )
    (net (code "14") (name "/I2C1_SDA_AUDIO") (class "Default")
      (node (ref "R97") (pin "1") (pinfunction "1_1") (pintype "passive"))
      (node (ref "U31") (pin "39") (pinfunction "SDA_39") (pintype "passive"))
    )
    (net (code "15") (name "/I2S1_LRCK_RX") (class "Default")
      (node (ref "R86") (pin "1") (pinfunction "1_1") (pintype "passive"))
    )
    (net (code "16") (name "/I2S1_LRCK_TX") (class "Default")
      (node (ref "R85") (pin "1") (pinfunction "1_1") (pintype "passive"))
    )
    (net (code "17") (name "/I2S1_SCLK") (class "Default")
      (node (ref "R84") (pin "1") (pinfunction "1_1") (pintype "passive"))
    )
    (net (code "18") (name "/I2S1_SDI0") (class "Default")
      (node (ref "R88") (pin "1") (pinfunction "1_1") (pintype "passive"))
    )
    (net (code "19") (name "/I2S1_SDO0") (class "Default")
      (node (ref "R87") (pin "1") (pinfunction "1_1") (pintype "passive"))
    )
    (net (code "20") (name "/I2S_CLK") (class "Default")
      (node (ref "R83") (pin "1") (pinfunction "1_1") (pintype "passive"))
    )
    (net (code "21") (name "/LDO1_EN") (class "Default")
      (node (ref "R89") (pin "1") (pinfunction "1_1") (pintype "passive"))
      (node (ref "R90") (pin "1") (pinfunction "1_1") (pintype "passive"))
      (node (ref "U31") (pin "44") (pinfunction "LDO1_EN_44") (pintype "passive"))
    )
    (net (code "22") (name "/LINE_IN_DET") (class "Default")
      (node (ref "ED62") (pin "1") (pinfunction "A1_1") (pintype "passive"))
      (node (ref "J103") (pin "LS") (pinfunction "LS_LS") (pintype "bidirectional"))
      (node (ref "J103") (pin "RS") (pinfunction "RS_RS") (pintype "bidirectional"))
      (node (ref "R80") (pin "2") (pinfunction "2_2") (pintype "passive"))
    )
    (net (code "23") (name "/LINE_IN_L") (class "Default")
      (node (ref "C102") (pin "1") (pinfunction "1_1") (pintype "passive"))
      (node (ref "ED29") (pin "1") (pinfunction "A1_1") (pintype "passive"))
      (node (ref "J103") (pin "L") (pinfunction "L_L") (pintype "bidirectional"))
      (node (ref "R286") (pin "1") (pinfunction "1_1") (pintype "passive"))
    )
    (net (code "24") (name "/LINE_IN_R") (class "Default")
      (node (ref "C103") (pin "1") (pinfunction "1_1") (pintype "passive"))
      (node (ref "ED30") (pin "1") (pinfunction "A1_1") (pintype "passive"))
      (node (ref "J103") (pin "R") (pinfunction "R_R") (pintype "bidirectional"))
      (node (ref "R285") (pin "1") (pinfunction "1_1") (pintype "passive"))
    )
    (net (code "25") (name "/LINE_OUT_L") (class "Default")
      (node (ref "R116") (pin "1") (pinfunction "1_1") (pintype "passive"))
      (node (ref "U31") (pin "16") (pinfunction "LOUTL_16") (pintype "passive"))
    )
    (net (code "26") (name "/LINE_OUT_R") (class "Default")
      (node (ref "R115") (pin "1") (pinfunction "1_1") (pintype "passive"))
      (node (ref "U31") (pin "17") (pinfunction "LOUTR_17") (pintype "passive"))
    )
    (net (code "27") (name "/LOUT") (class "Default")
      (node (ref "ED24") (pin "1") (pinfunction "A1_1") (pintype "passive"))
      (node (ref "J16") (pin "L") (pinfunction "L_L") (pintype "bidirectional"))
      (node (ref "R105") (pin "1") (pinfunction "1_1") (pintype "passive"))
    )
    (net (code "28") (name "/MIC_IN1N") (class "Default")
      (node (ref "C124") (pin "1") (pinfunction "1_1") (pintype "passive"))
      (node (ref "C143") (pin "2") (pinfunction "2_2") (pintype "passive"))
      (node (ref "C145") (pin "1") (pinfunction "1_1") (pintype "passive"))
      (node (ref "ED23") (pin "1") (pinfunction "A1_1") (pintype "passive"))
      (node (ref "J14") (pin "1") (pinfunction "1_1") (pintype "passive"))
      (node (ref "R107") (pin "1") (pinfunction "1_1") (pintype "passive"))
      (node (ref "R296") (pin "2") (pinfunction "2_2") (pintype "passive"))
    )
    (net (code "29") (name "/MIC_IN1P") (class "Default")
      (node (ref "C123") (pin "1") (pinfunction "1_1") (pintype "passive"))
      (node (ref "C143") (pin "1") (pinfunction "1_1") (pintype "passive"))
      (node (ref "C144") (pin "1") (pinfunction "1_1") (pintype "passive"))
      (node (ref "ED20") (pin "1") (pinfunction "A1_1") (pintype "passive"))
      (node (ref "J14") (pin "2") (pinfunction "2_2") (pintype "passive"))
      (node (ref "R100") (pin "2") (pinfunction "2_2") (pintype "passive"))
      (node (ref "R295") (pin "2") (pinfunction "2_2") (pintype "passive"))
    )
    (net (code "30") (name "/MIC_IN2P") (class "Default")
      (node (ref "C32") (pin "2") (pinfunction "2_2") (pintype "passive"))
      (node (ref "ED22") (pin "1") (pinfunction "A1_1") (pintype "passive"))
      (node (ref "J16") (pin "COM2") (pinfunction "COM2_COM2") (pintype "bidirectional"))
      (node (ref "R99") (pin "1") (pinfunction "1_1") (pintype "passive"))
    )
    (net (code "31") (name "/ROUT") (class "Default")
      (node (ref "ED21") (pin "1") (pinfunction "A1_1") (pintype "passive"))
      (node (ref "J16") (pin "R") (pinfunction "R_R") (pintype "bidirectional"))
      (node (ref "R104") (pin "1") (pinfunction "1_1") (pintype "passive"))
    )
    (net (code "32") (name "/SPK_LN") (class "Default")
      (node (ref "C149") (pin "2") (pinfunction "2_2") (pintype "passive"))
      (node (ref "ED26") (pin "1") (pinfunction "A1_1") (pintype "passive"))
      (node (ref "FB3") (pin "2") (pinfunction "2_2") (pintype "passive"))
      (node (ref "J17") (pin "2") (pinfunction "2_2") (pintype "passive"))
    )
    (net (code "33") (name "/SPK_LN1") (class "Default")
      (node (ref "FB3") (pin "1") (pinfunction "1_1") (pintype "passive"))
      (node (ref "U31") (pin "48") (pinfunction "SPO_LN_48") (pintype "passive"))
    )
    (net (code "34") (name "/SPK_LP") (class "Default")
      (node (ref "C148") (pin "1") (pinfunction "1_1") (pintype "passive"))
      (node (ref "ED25") (pin "1") (pinfunction "A1_1") (pintype "passive"))
      (node (ref "FB2") (pin "2") (pinfunction "2_2") (pintype "passive"))
      (node (ref "J17") (pin "1") (pinfunction "1_1") (pintype "passive"))
    )
    (net (code "35") (name "/SPK_LP1") (class "Default")
      (node (ref "FB2") (pin "1") (pinfunction "1_1") (pintype "passive"))
      (node (ref "U31") (pin "1") (pinfunction "SPO_LP_1") (pintype "passive"))
    )
    (net (code "36") (name "/SPK_RN") (class "Default")
      (node (ref "C156") (pin "2") (pinfunction "2_2") (pintype "passive"))
      (node (ref "ED32") (pin "1") (pinfunction "A1_1") (pintype "passive"))
      (node (ref "FB5") (pin "2") (pinfunction "2_2") (pintype "passive"))
      (node (ref "J17") (pin "4") (pinfunction "4_4") (pintype "passive"))
    )
    (net (code "37") (name "/SPK_RN1") (class "Default")
      (node (ref "FB5") (pin "1") (pinfunction "1_1") (pintype "passive"))
      (node (ref "U31") (pin "47") (pinfunction "SPO_RN_47") (pintype "passive"))
    )
    (net (code "38") (name "/SPK_RP") (class "Default")
      (node (ref "C153") (pin "1") (pinfunction "1_1") (pintype "passive"))
      (node (ref "ED31") (pin "1") (pinfunction "A1_1") (pintype "passive"))
      (node (ref "FB4") (pin "2") (pinfunction "2_2") (pintype "passive"))
      (node (ref "J17") (pin "3") (pinfunction "3_3") (pintype "passive"))
    )
    (net (code "39") (name "/SPK_RP1") (class "Default")
      (node (ref "FB4") (pin "1") (pinfunction "1_1") (pintype "passive"))
      (node (ref "U31") (pin "45") (pinfunction "SPO_RP_45") (pintype "passive"))
    )
    (net (code "40") (name "AVDD18_REF") (class "Default")
      (node (ref "C138") (pin "1") (pinfunction "1_1") (pintype "passive"))
      (node (ref "C139") (pin "1") (pinfunction "1_1") (pintype "passive"))
      (node (ref "R91") (pin "2") (pinfunction "2_2") (pintype "passive"))
      (node (ref "U31") (pin "10") (pinfunction "DACRFE_10") (pintype "passive"))
    )
    (net (code "41") (name "GND") (class "Default")
      (node (ref "C101") (pin "2") (pinfunction "2_2") (pintype "passive"))
      (node (ref "C116") (pin "2") (pinfunction "2_2") (pintype "passive"))
      (node (ref "C117") (pin "2") (pinfunction "2_2") (pintype "passive"))
      (node (ref "C118") (pin "2") (pinfunction "2_2") (pintype "passive"))
      (node (ref "C119") (pin "2") (pinfunction "2_2") (pintype "passive"))
      (node (ref "C121") (pin "2") (pinfunction "2_2") (pintype "passive"))
      (node (ref "C122") (pin "2") (pinfunction "2_2") (pintype "passive"))
      (node (ref "C127") (pin "2") (pinfunction "2_2") (pintype "passive"))
      (node (ref "C129") (pin "2") (pinfunction "2_2") (pintype "passive"))
      (node (ref "C130") (pin "2") (pinfunction "2_2") (pintype "passive"))
      (node (ref "C131") (pin "2") (pinfunction "2_2") (pintype "passive"))
      (node (ref "C132") (pin "1") (pinfunction "1_1") (pintype "passive"))
      (node (ref "C133") (pin "1") (pinfunction "1_1") (pintype "passive"))
      (node (ref "C134") (pin "2") (pinfunction "2_2") (pintype "passive"))
      (node (ref "C135") (pin "2") (pinfunction "2_2") (pintype "passive"))
      (node (ref "C136") (pin "2") (pinfunction "2_2") (pintype "passive"))
      (node (ref "C137") (pin "2") (pinfunction "2_2") (pintype "passive"))
      (node (ref "C138") (pin "2") (pinfunction "2_2") (pintype "passive"))
      (node (ref "C139") (pin "2") (pinfunction "2_2") (pintype "passive"))
      (node (ref "C140") (pin "2") (pinfunction "2_2") (pintype "passive"))
      (node (ref "C141") (pin "2") (pinfunction "2_2") (pintype "passive"))
      (node (ref "C142") (pin "2") (pinfunction "2_2") (pintype "passive"))
      (node (ref "C144") (pin "2") (pinfunction "2_2") (pintype "passive"))
      (node (ref "C145") (pin "2") (pinfunction "2_2") (pintype "passive"))
      (node (ref "C146") (pin "1") (pinfunction "1_1") (pintype "passive"))
      (node (ref "C147") (pin "1") (pinfunction "1_1") (pintype "passive"))
      (node (ref "C148") (pin "2") (pinfunction "2_2") (pintype "passive"))
      (node (ref "C149") (pin "1") (pinfunction "1_1") (pintype "passive"))
      (node (ref "C153") (pin "2") (pinfunction "2_2") (pintype "passive"))
      (node (ref "C156") (pin "1") (pinfunction "1_1") (pintype "passive"))
      (node (ref "ED19") (pin "2") (pinfunction "A2_2") (pintype "passive"))
      (node (ref "ED20") (pin "2") (pinfunction "A2_2") (pintype "passive"))
      (node (ref "ED21") (pin "2") (pinfunction "A2_2") (pintype "passive"))
      (node (ref "ED22") (pin "2") (pinfunction "A2_2") (pintype "passive"))
      (node (ref "ED23") (pin "2") (pinfunction "A2_2") (pintype "passive"))
      (node (ref "ED24") (pin "2") (pinfunction "A2_2") (pintype "passive"))
      (node (ref "ED25") (pin "2") (pinfunction "A2_2") (pintype "passive"))
      (node (ref "ED26") (pin "2") (pinfunction "A2_2") (pintype "passive"))
      (node (ref "ED27") (pin "2") (pinfunction "A2_2") (pintype "passive"))
      (node (ref "ED28") (pin "2") (pinfunction "A2_2") (pintype "passive"))
      (node (ref "ED29") (pin "2") (pinfunction "A2_2") (pintype "passive"))
      (node (ref "ED30") (pin "2") (pinfunction "A2_2") (pintype "passive"))
      (node (ref "ED31") (pin "2") (pinfunction "A2_2") (pintype "passive"))
      (node (ref "ED32") (pin "2") (pinfunction "A2_2") (pintype "passive"))
      (node (ref "ED62") (pin "2") (pinfunction "A2_2") (pintype "passive"))
      (node (ref "J103") (pin "COM1") (pinfunction "COM1_COM1") (pintype "bidirectional"))
      (node (ref "J16") (pin "COM1") (pinfunction "COM1_COM1") (pintype "bidirectional"))
      (node (ref "J44") (pin "2") (pinfunction "2_2") (pintype "passive"))
      (node (ref "R107") (pin "2") (pinfunction "2_2") (pintype "passive"))
      (node (ref "R108") (pin "2") (pinfunction "2_2") (pintype "passive"))
      (node (ref "R109") (pin "1") (pinfunction "1_1") (pintype "passive"))
      (node (ref "R110") (pin "1") (pinfunction "1_1") (pintype "passive"))
      (node (ref "R112") (pin "2") (pinfunction "2_2") (pintype "passive"))
      (node (ref "R285") (pin "2") (pinfunction "2_2") (pintype "passive"))
      (node (ref "R286") (pin "2") (pinfunction "2_2") (pintype "passive"))
      (node (ref "R90") (pin "2") (pinfunction "2_2") (pintype "passive"))
      (node (ref "U31") (pin "22") (pinfunction "CPGND_22") (pintype "passive"))
      (node (ref "U31") (pin "25") (pinfunction "HPOFB_25") (pintype "passive"))
      (node (ref "U31") (pin "49") (pinfunction "PADGND_49") (pintype "passive"))
      (node (ref "U31") (pin "9") (pinfunction "AGND_9") (pintype "passive"))
    )
    (net (code "42") (name "MICBIAS1") (class "Default")
      (node (ref "R101") (pin "2") (pinfunction "2_2") (pintype "passive"))
      (node (ref "R98") (pin "2") (pinfunction "2_2") (pintype "passive"))
      (node (ref "U31") (pin "4") (pinfunction "MICBAIS1_4") (pintype "passive"))
    )
    (net (code "43") (name "Net-(C140-Pad1)") (class "Default")
      (node (ref "C140") (pin "1") (pinfunction "1_1") (pintype "passive"))
      (node (ref "R98") (pin "1") (pinfunction "1_1") (pintype "passive"))
      (node (ref "R99") (pin "2") (pinfunction "2_2") (pintype "passive"))
    )
    (net (code "44") (name "Net-(C141-Pad1)") (class "Default")
      (node (ref "C141") (pin "1") (pinfunction "1_1") (pintype "passive"))
      (node (ref "C142") (pin "1") (pinfunction "1_1") (pintype "passive"))
      (node (ref "R100") (pin "1") (pinfunction "1_1") (pintype "passive"))
      (node (ref "R101") (pin "1") (pinfunction "1_1") (pintype "passive"))
    )
    (net (code "45") (name "Net-(ED27-A1)") (class "Default")
      (node (ref "ED27") (pin "1") (pinfunction "A1_1") (pintype "passive"))
      (node (ref "J44") (pin "1") (pinfunction "1_1") (pintype "passive"))
      (node (ref "R115") (pin "2") (pinfunction "2_2") (pintype "passive"))
    )
    (net (code "46") (name "Net-(ED28-A1)") (class "Default")
      (node (ref "ED28") (pin "1") (pinfunction "A1_1") (pintype "passive"))
      (node (ref "J44") (pin "3") (pinfunction "3_3") (pintype "passive"))
      (node (ref "R116") (pin "2") (pinfunction "2_2") (pintype "passive"))
    )
    (net (code "47") (name "Net-(Q6-D)") (class "Default")
      (node (ref "EC1") (pin "2") (pinfunction "2_2") (pintype "passive"))
      (node (ref "Q6") (pin "1") (pinfunction "D_1") (pintype "passive"))
      (node (ref "R102") (pin "2") (pinfunction "2_2") (pintype "passive"))
    )
    (net (code "48") (name "Net-(Q6-G)") (class "Default")
      (node (ref "C147") (pin "2") (pinfunction "2_2") (pintype "passive"))
      (node (ref "Q6") (pin "3") (pinfunction "G_3") (pintype "passive"))
      (node (ref "Q7") (pin "3") (pinfunction "G_3") (pintype "passive"))
      (node (ref "R111") (pin "1") (pinfunction "1_1") (pintype "passive"))
    )
    (net (code "49") (name "Net-(Q6-S)") (class "Default")
      (node (ref "Q6") (pin "2") (pinfunction "S_2") (pintype "passive"))
      (node (ref "R102") (pin "1") (pinfunction "1_1") (pintype "passive"))
      (node (ref "R104") (pin "2") (pinfunction "2_2") (pintype "passive"))
      (node (ref "R110") (pin "2") (pinfunction "2_2") (pintype "passive"))
    )
    (net (code "50") (name "Net-(Q7-D)") (class "Default")
      (node (ref "EC2") (pin "2") (pinfunction "2_2") (pintype "passive"))
      (node (ref "Q7") (pin "1") (pinfunction "D_1") (pintype "passive"))
      (node (ref "R103") (pin "2") (pinfunction "2_2") (pintype "passive"))
    )
    (net (code "51") (name "Net-(Q7-S)") (class "Default")
      (node (ref "Q7") (pin "2") (pinfunction "S_2") (pintype "passive"))
      (node (ref "R103") (pin "1") (pinfunction "1_1") (pintype "passive"))
      (node (ref "R105") (pin "2") (pinfunction "2_2") (pintype "passive"))
      (node (ref "R109") (pin "2") (pinfunction "2_2") (pintype "passive"))
    )
    (net (code "52") (name "Net-(U31-ADCDAT1)") (class "Default")
      (node (ref "R88") (pin "2") (pinfunction "2_2") (pintype "passive"))
      (node (ref "U31") (pin "34") (pinfunction "ADCDAT1_34") (pintype "passive"))
    )
    (net (code "53") (name "Net-(U31-ADCDAT2)") (class "Default")
      (node (ref "R95") (pin "2") (pinfunction "2_2") (pintype "passive"))
      (node (ref "U31") (pin "32") (pinfunction "ADCDAT2_32") (pintype "passive"))
    )
    (net (code "54") (name "Net-(U31-BCLK1)") (class "Default")
      (node (ref "R84") (pin "2") (pinfunction "2_2") (pintype "passive"))
      (node (ref "U31") (pin "36") (pinfunction "BCLK1_36") (pintype "passive"))
    )
    (net (code "55") (name "Net-(U31-BLCK2)") (class "Default")
      (node (ref "R92") (pin "2") (pinfunction "2_2") (pintype "passive"))
      (node (ref "U31") (pin "30") (pinfunction "BLCK2_30") (pintype "passive"))
    )
    (net (code "56") (name "Net-(U31-CPN1)") (class "Default")
      (node (ref "C120") (pin "2") (pinfunction "2_2") (pintype "passive"))
      (node (ref "U31") (pin "21") (pinfunction "CPN1_21") (pintype "passive"))
    )
    (net (code "57") (name "Net-(U31-CPN2)") (class "Default")
      (node (ref "C125") (pin "2") (pinfunction "2_2") (pintype "passive"))
      (node (ref "U31") (pin "18") (pinfunction "CPN2_18") (pintype "passive"))
    )
    (net (code "58") (name "Net-(U31-CPP1)") (class "Default")
      (node (ref "C120") (pin "1") (pinfunction "1_1") (pintype "passive"))
      (node (ref "U31") (pin "20") (pinfunction "CPP1_20") (pintype "passive"))
    )
    (net (code "59") (name "Net-(U31-CPP2)") (class "Default")
      (node (ref "C125") (pin "1") (pinfunction "1_1") (pintype "passive"))
      (node (ref "U31") (pin "19") (pinfunction "CPP2_19") (pintype "passive"))
    )
    (net (code "60") (name "Net-(U31-CPVEE)") (class "Default")
      (node (ref "C122") (pin "1") (pinfunction "1_1") (pintype "passive"))
      (node (ref "U31") (pin "27") (pinfunction "CPVEE_27") (pintype "passive"))
    )
    (net (code "61") (name "Net-(U31-CPVPP)") (class "Default")
      (node (ref "C121") (pin "1") (pinfunction "1_1") (pintype "passive"))
      (node (ref "U31") (pin "24") (pinfunction "CPVPP_24") (pintype "passive"))
    )
    (net (code "62") (name "Net-(U31-DACDAT1)") (class "Default")
      (node (ref "R87") (pin "2") (pinfunction "2_2") (pintype "passive"))
      (node (ref "U31") (pin "33") (pinfunction "DACDAT1_33") (pintype "passive"))
    )
    (net (code "63") (name "Net-(U31-DACDAT2)") (class "Default")
      (node (ref "R94") (pin "2") (pinfunction "2_2") (pintype "passive"))
      (node (ref "U31") (pin "31") (pinfunction "DACDAT2_31") (pintype "passive"))
    )
    (net (code "64") (name "Net-(U31-IN1N{slash}DMIC2_DAT{slash}JD1)") (class "Default")
      (node (ref "C124") (pin "2") (pinfunction "2_2") (pintype "passive"))
      (node (ref "U31") (pin "6") (pinfunction "IN1N/DMIC2_DAT/JD1_6") (pintype "passive"))
    )
    (net (code "65") (name "Net-(U31-IN1P{slash}DMIC1_DAT)") (class "Default")
      (node (ref "C123") (pin "2") (pinfunction "2_2") (pintype "passive"))
      (node (ref "U31") (pin "5") (pinfunction "IN1P/DMIC1_DAT_5") (pintype "passive"))
    )
    (net (code "66") (name "Net-(U31-IN2N{slash}JD2)") (class "Default")
      (node (ref "C103") (pin "2") (pinfunction "2_2") (pintype "passive"))
      (node (ref "U31") (pin "8") (pinfunction "IN2N/JD2_8") (pintype "passive"))
    )
    (net (code "67") (name "Net-(U31-IN2P)") (class "Default")
      (node (ref "C102") (pin "2") (pinfunction "2_2") (pintype "passive"))
      (node (ref "U31") (pin "7") (pinfunction "IN2P_7") (pintype "passive"))
    )
    (net (code "68") (name "Net-(U31-LRCLK1)") (class "Default")
      (node (ref "R85") (pin "2") (pinfunction "2_2") (pintype "passive"))
      (node (ref "R86") (pin "2") (pinfunction "2_2") (pintype "passive"))
      (node (ref "U31") (pin "35") (pinfunction "LRCLK1_35") (pintype "passive"))
    )
    (net (code "69") (name "Net-(U31-LRCLK2)") (class "Default")
      (node (ref "R93") (pin "2") (pinfunction "2_2") (pintype "passive"))
      (node (ref "U31") (pin "29") (pinfunction "LRCLK2_29") (pintype "passive"))
    )
    (net (code "70") (name "Net-(U31-MCLK)") (class "Default")
      (node (ref "R83") (pin "2") (pinfunction "2_2") (pintype "passive"))
      (node (ref "U31") (pin "37") (pinfunction "MCLK_37") (pintype "passive"))
    )
    (net (code "71") (name "Net-(U31-MONON)") (class "Default")
      (node (ref "C101") (pin "1") (pinfunction "1_1") (pintype "passive"))
      (node (ref "U31") (pin "14") (pinfunction "MONON_14") (pintype "passive"))
    )
    (net (code "72") (name "Net-(U31-MONOP)") (class "Default")
      (node (ref "C32") (pin "1") (pinfunction "1_1") (pintype "passive"))
      (node (ref "U31") (pin "13") (pinfunction "MONOP_13") (pintype "passive"))
    )
    (net (code "73") (name "Net-(U31-VREF1)") (class "Default")
      (node (ref "C132") (pin "2") (pinfunction "2_2") (pintype "passive"))
      (node (ref "U31") (pin "11") (pinfunction "VREF1_11") (pintype "passive"))
    )
    (net (code "74") (name "Net-(U31-VREF2)") (class "Default")
      (node (ref "C133") (pin "2") (pinfunction "2_2") (pintype "passive"))
      (node (ref "U31") (pin "12") (pinfunction "VREF2_12") (pintype "passive"))
    )
    (net (code "75") (name "VCCA1V8_CODEC") (class "Default")
      (node (ref "C134") (pin "1") (pinfunction "1_1") (pintype "passive"))
      (node (ref "C135") (pin "1") (pinfunction "1_1") (pintype "passive"))
      (node (ref "C136") (pin "1") (pinfunction "1_1") (pintype "passive"))
      (node (ref "C137") (pin "1") (pinfunction "1_1") (pintype "passive"))
      (node (ref "R89") (pin "2") (pinfunction "2_2") (pintype "passive"))
      (node (ref "R91") (pin "1") (pinfunction "1_1") (pintype "passive"))
      (node (ref "U31") (pin "15") (pinfunction "AVDD_15") (pintype "passive"))
      (node (ref "U31") (pin "23") (pinfunction "CPVDD_23") (pintype "passive"))
      (node (ref "U31") (pin "43") (pinfunction "DBVDD_43") (pintype "passive"))
    )
    (net (code "76") (name "VCCA1V8_S3") (class "Default")
      (node (ref "R106") (pin "2") (pinfunction "2_2") (pintype "passive"))
      (node (ref "R80") (pin "1") (pinfunction "1_1") (pintype "passive"))
    )
    (net (code "77") (name "VCCA3V0_CODEC") (class "Default")
      (node (ref "C127") (pin "1") (pinfunction "1_1") (pintype "passive"))
      (node (ref "C129") (pin "1") (pinfunction "1_1") (pintype "passive"))
      (node (ref "U31") (pin "3") (pinfunction "MICVDD_3") (pintype "passive"))
    )
    (net (code "78") (name "VCC_SPK") (class "Default")
      (node (ref "C118") (pin "1") (pinfunction "1_1") (pintype "passive"))
      (node (ref "C119") (pin "1") (pinfunction "1_1") (pintype "passive"))
      (node (ref "FB1") (pin "2") (pinfunction "2_2") (pintype "passive"))
      (node (ref "U31") (pin "2") (pinfunction "SPKVDDL_2") (pintype "passive"))
      (node (ref "U31") (pin "46") (pinfunction "SPKVDDR_46") (pintype "passive"))
    )
    (net (code "79") (name "VCC_SYS") (class "Default")
      (node (ref "C116") (pin "1") (pinfunction "1_1") (pintype "passive"))
      (node (ref "C117") (pin "1") (pinfunction "1_1") (pintype "passive"))
      (node (ref "FB1") (pin "1") (pinfunction "1_1") (pintype "passive"))
    )
    (net (code "80") (name "VDD_CODEC") (class "Default")
      (node (ref "C130") (pin "1") (pinfunction "1_1") (pintype "passive"))
      (node (ref "C131") (pin "1") (pinfunction "1_1") (pintype "passive"))
      (node (ref "U31") (pin "42") (pinfunction "DCVDD_42") (pintype "passive"))
    )
    (net (code "81") (name "unconnected-(J16-PadLS)") (class "Default")
      (node (ref "J16") (pin "LS") (pinfunction "LS_LS") (pintype "bidirectional+no_connect"))
    )
    (net (code "82") (name "unconnected-(J103-PadCOM2)") (class "Default")
      (node (ref "J103") (pin "COM2") (pinfunction "COM2_COM2") (pintype "bidirectional+no_connect"))
    )
    (net (code "83") (name "unconnected-(U31-DMIC_SCL-Pad41)") (class "Default")
      (node (ref "U31") (pin "41") (pinfunction "DMIC_SCL_41") (pintype "passive+no_connect"))
    )
    (net (code "84") (name "unconnected-(U31-GIPO{slash}IRQ-Pad40)") (class "Default")
      (node (ref "U31") (pin "40") (pinfunction "GIPO/IRQ_40") (pintype "passive+no_connect"))
    )
  )
)
